# Inverter_Power_Stage.net
KiCad netlist of a schematic drawn in Altium Designer
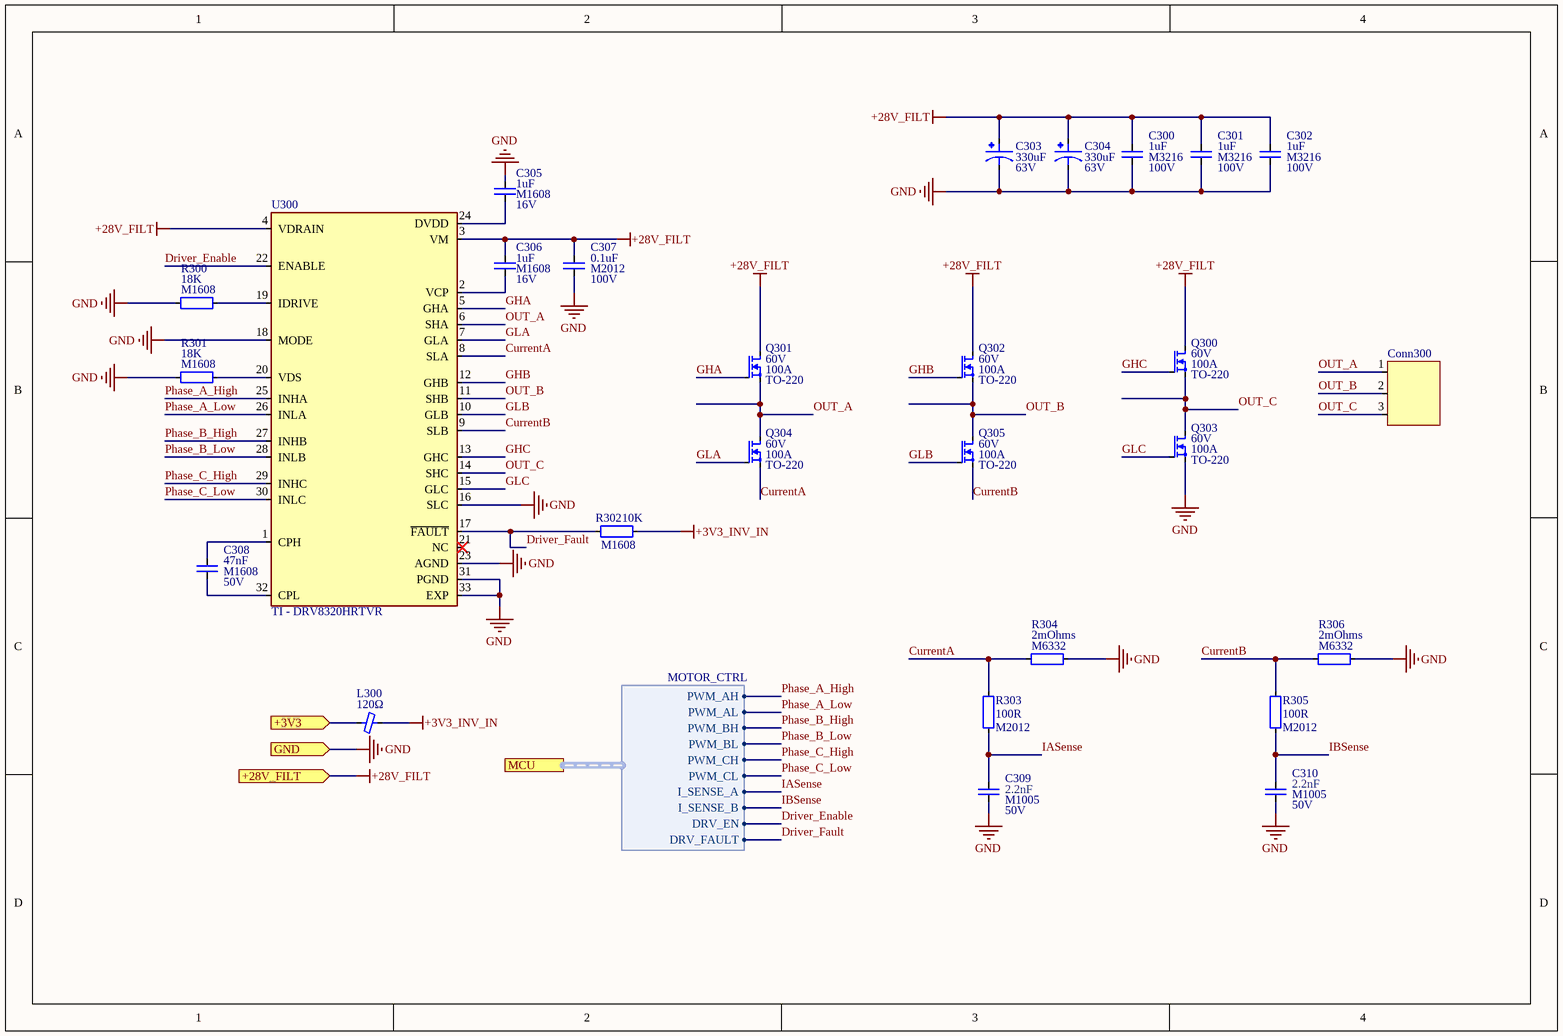
[diagram p0: Inverter_Power_Stage.SchDoc]

(export (version "E")
  (design (tool "Eeschema 10.0.6"))
  (components
    (comp (ref "C300")
      (value "1uF")
      (footprint "Capacitor_Seramic_M3216_I1206")
      (description "Cap, Cer, 1uF, 100V, M3216")
      (fields
        (field (name "TOLERANCE") "±10%")
        (field (name "MANUFACTURER PART NUMBER") "C3216X7R2A105K160AA")
        (field (name "PACKAGE") "M3216")
        (field (name "RATED VOLTAGE") "100V")
      )
      (libsource (lib "Capacitor") (part "Capacitor_Seramic"))
    )
    (comp (ref "C301")
      (value "1uF")
      (footprint "Capacitor_Seramic_M3216_I1206")
      (description "Cap, Cer, 1uF, 100V, M3216")
      (fields
        (field (name "TOLERANCE") "±10%")
        (field (name "MANUFACTURER PART NUMBER") "C3216X7R2A105K160AA")
        (field (name "PACKAGE") "M3216")
        (field (name "RATED VOLTAGE") "100V")
      )
      (libsource (lib "Capacitor") (part "Capacitor_Seramic"))
    )
    (comp (ref "C302")
      (value "1uF")
      (footprint "Capacitor_Seramic_M3216_I1206")
      (description "Cap, Cer, 1uF, 100V, M3216")
      (fields
        (field (name "TOLERANCE") "±10%")
        (field (name "MANUFACTURER PART NUMBER") "C3216X7R2A105K160AA")
        (field (name "PACKAGE") "M3216")
        (field (name "RATED VOLTAGE") "100V")
      )
      (libsource (lib "Capacitor") (part "Capacitor_Seramic"))
    )
    (comp (ref "C303")
      (value "330uF")
      (footprint "Capacitor_Aluminum_TH")
      (description "220F 63V Aluminum Electrolytic Capacitors Radial, Can 10000 Hrs @ 105C")
      (fields
        (field (name "MANUFACTURER") "Panasonic Electronic Components")
        (field (name "MANUFACTURER PART NUMBER") "EEU-FR1J331")
        (field (name "RATED VOLTAGE") "63V")
      )
      (libsource (lib "Capacitor") (part "Capacitor_Aluminum_TH"))
    )
    (comp (ref "C304")
      (value "330uF")
      (footprint "Capacitor_Aluminum_TH")
      (description "220F 63V Aluminum Electrolytic Capacitors Radial, Can 10000 Hrs @ 105C")
      (fields
        (field (name "MANUFACTURER") "Panasonic Electronic Components")
        (field (name "MANUFACTURER PART NUMBER") "EEU-FR1J331")
        (field (name "RATED VOLTAGE") "63V")
      )
      (libsource (lib "Capacitor") (part "Capacitor_Aluminum_TH"))
    )
    (comp (ref "C305")
      (value "1uF")
      (footprint "Capacitor_Seramic_M1608_I0603")
      (description "Cap, Cer, 1uF, 16V, M1608")
      (fields
        (field (name "TOLERANCE") "±10%")
        (field (name "MANUFACTURER PART NUMBER") "CL10B105KO8NNNC")
        (field (name "PACKAGE") "M1608")
        (field (name "RATED VOLTAGE") "16V")
      )
      (libsource (lib "Capacitor") (part "Capacitor_Seramic"))
    )
    (comp (ref "C306")
      (value "1uF")
      (footprint "Capacitor_Seramic_M1608_I0603")
      (description "Cap, Cer, 1uF, 16V, M1608")
      (fields
        (field (name "TOLERANCE") "±10%")
        (field (name "MANUFACTURER PART NUMBER") "CL10B105KO8NNNC")
        (field (name "PACKAGE") "M1608")
        (field (name "RATED VOLTAGE") "16V")
      )
      (libsource (lib "Capacitor") (part "Capacitor_Seramic"))
    )
    (comp (ref "C307")
      (value "0.1uF")
      (footprint "Capacitor_Seramic_M2012_I0805")
      (description "Cap, Cer, 0.1uF, 100V, M2012")
      (fields
        (field (name "TOLERANCE") "±10%")
        (field (name "MANUFACTURER PART NUMBER") "C2012X7R2A104K125AA")
        (field (name "PACKAGE") "M2012")
        (field (name "RATED VOLTAGE") "100V")
      )
      (libsource (lib "Capacitor") (part "Capacitor_Seramic"))
    )
    (comp (ref "C308")
      (value "47nF")
      (footprint "Capacitor_Seramic_M1608_I0603")
      (description "Cap, Cer, 47nF, 50V, M1608")
      (fields
        (field (name "TOLERANCE") "±10%")
        (field (name "MANUFACTURER PART NUMBER") "C3216X7R2A105K160AA")
        (field (name "PACKAGE") "M1608")
        (field (name "RATED VOLTAGE") "50V")
      )
      (libsource (lib "Capacitor") (part "Capacitor_Seramic"))
    )
    (comp (ref "C309")
      (value "2.2nF")
      (footprint "Capacitor_Seramic_M1005_I0402")
      (description "Cap, Cer, 2.2nF, 50V, M1005")
      (fields
        (field (name "TOLERANCE") "10%")
        (field (name "MANUFACTURER PART NUMBER") "GCM155R71H223KA55D")
        (field (name "PACKAGE") "M1005")
        (field (name "RATED VOLTAGE") "50V")
      )
      (libsource (lib "Capacitor") (part "Capacitor_Seramic"))
    )
    (comp (ref "C310")
      (value "2.2nF")
      (footprint "Capacitor_Seramic_M1005_I0402")
      (description "Cap, Cer, 2.2nF, 50V, M1005")
      (fields
        (field (name "TOLERANCE") "10%")
        (field (name "MANUFACTURER PART NUMBER") "GCM155R71H223KA55D")
        (field (name "PACKAGE") "M1005")
        (field (name "RATED VOLTAGE") "50V")
      )
      (libsource (lib "Capacitor") (part "Capacitor_Seramic"))
    )
    (comp (ref "Conn300")
      (value "Connector - 3P")
      (footprint "Phoenix- 3Pin, 1714968")
      (fields
        (field (name "VOLTAGE") "300V")
        (field (name "MANUFACTURER PART NUMBER") "1714968")
        (field (name "MANUFACTURER") "Phoenix Contact")
      )
      (libsource (lib "Connector - Terminal Block") (part "Connector - 3P"))
    )
    (comp (ref "L300")
      (value "120Ω")
      (footprint "Ferrite_Bead_Smd_M1608_I0603")
      (fields
        (field (name "MANUFACTURER PART NUMBER") "BLM18PG121SN1D")
        (field (name "MANUFACTURER") "Murata Electronics")
        (field (name "Comment") "Ferrite Bead")
      )
      (libsource (lib "Inductor") (part "Ferrite Bead"))
    )
    (comp (ref "Q300")
      (value "Mosfet, N-Channel - TI - CSD18532KCS")
      (footprint "TO-220-3, Mosfet, N-Channel")
      (description "Mosfet, N-Channel - Texas Instruments - CSD18532KCS")
      (fields
        (field (name "MANUFACTURER PART NUMBER") "CSD18532KCS")
        (field (name "MANUFACTURER") "Texas Instruments")
        (field (name "CURRENT") "100A")
        (field (name "VOLTAGE") "60V")
        (field (name "PACKAGE") "TO-220")
        (field (name "COMPONENTLINK1URL") "C:\\Users\\User\\OneDrive - Karadeniz Teknik University\\Masaüstü\\pcb\\kütüphane\\Datasheet\\csd18532kcs.pdf")
      )
      (libsource (lib "Transistor") (part "Mosfet, N-Channel - TI - CSD18532KCS"))
    )
    (comp (ref "Q301")
      (value "Mosfet, N-Channel - TI - CSD18532KCS")
      (footprint "TO-220-3, Mosfet, N-Channel")
      (description "Mosfet, N-Channel - Texas Instruments - CSD18532KCS")
      (fields
        (field (name "MANUFACTURER PART NUMBER") "CSD18532KCS")
        (field (name "MANUFACTURER") "Texas Instruments")
        (field (name "CURRENT") "100A")
        (field (name "VOLTAGE") "60V")
        (field (name "PACKAGE") "TO-220")
        (field (name "COMPONENTLINK1URL") "C:\\Users\\User\\OneDrive - Karadeniz Teknik University\\Masaüstü\\pcb\\kütüphane\\Datasheet\\csd18532kcs.pdf")
      )
      (libsource (lib "Transistor") (part "Mosfet, N-Channel - TI - CSD18532KCS"))
    )
    (comp (ref "Q302")
      (value "Mosfet, N-Channel - TI - CSD18532KCS")
      (footprint "TO-220-3, Mosfet, N-Channel")
      (description "Mosfet, N-Channel - Texas Instruments - CSD18532KCS")
      (fields
        (field (name "MANUFACTURER PART NUMBER") "CSD18532KCS")
        (field (name "MANUFACTURER") "Texas Instruments")
        (field (name "CURRENT") "100A")
        (field (name "VOLTAGE") "60V")
        (field (name "PACKAGE") "TO-220")
        (field (name "COMPONENTLINK1URL") "C:\\Users\\User\\OneDrive - Karadeniz Teknik University\\Masaüstü\\pcb\\kütüphane\\Datasheet\\csd18532kcs.pdf")
      )
      (libsource (lib "Transistor") (part "Mosfet, N-Channel - TI - CSD18532KCS"))
    )
    (comp (ref "Q303")
      (value "Mosfet, N-Channel - TI - CSD18532KCS")
      (footprint "TO-220-3, Mosfet, N-Channel")
      (description "Mosfet, N-Channel - Texas Instruments - CSD18532KCS")
      (fields
        (field (name "MANUFACTURER PART NUMBER") "CSD18532KCS")
        (field (name "MANUFACTURER") "Texas Instruments")
        (field (name "CURRENT") "100A")
        (field (name "VOLTAGE") "60V")
        (field (name "PACKAGE") "TO-220")
        (field (name "COMPONENTLINK1URL") "C:\\Users\\User\\OneDrive - Karadeniz Teknik University\\Masaüstü\\pcb\\kütüphane\\Datasheet\\csd18532kcs.pdf")
      )
      (libsource (lib "Transistor") (part "Mosfet, N-Channel - TI - CSD18532KCS"))
    )
    (comp (ref "Q304")
      (value "Mosfet, N-Channel - TI - CSD18532KCS")
      (footprint "TO-220-3, Mosfet, N-Channel")
      (description "Mosfet, N-Channel - Texas Instruments - CSD18532KCS")
      (fields
        (field (name "MANUFACTURER PART NUMBER") "CSD18532KCS")
        (field (name "MANUFACTURER") "Texas Instruments")
        (field (name "CURRENT") "100A")
        (field (name "VOLTAGE") "60V")
        (field (name "PACKAGE") "TO-220")
        (field (name "COMPONENTLINK1URL") "C:\\Users\\User\\OneDrive - Karadeniz Teknik University\\Masaüstü\\pcb\\kütüphane\\Datasheet\\csd18532kcs.pdf")
      )
      (libsource (lib "Transistor") (part "Mosfet, N-Channel - TI - CSD18532KCS"))
    )
    (comp (ref "Q305")
      (value "Mosfet, N-Channel - TI - CSD18532KCS")
      (footprint "TO-220-3, Mosfet, N-Channel")
      (description "Mosfet, N-Channel - Texas Instruments - CSD18532KCS")
      (fields
        (field (name "MANUFACTURER PART NUMBER") "CSD18532KCS")
        (field (name "MANUFACTURER") "Texas Instruments")
        (field (name "CURRENT") "100A")
        (field (name "VOLTAGE") "60V")
        (field (name "PACKAGE") "TO-220")
        (field (name "COMPONENTLINK1URL") "C:\\Users\\User\\OneDrive - Karadeniz Teknik University\\Masaüstü\\pcb\\kütüphane\\Datasheet\\csd18532kcs.pdf")
      )
      (libsource (lib "Transistor") (part "Mosfet, N-Channel - TI - CSD18532KCS"))
    )
    (comp (ref "R300")
      (value "18K")
      (footprint "Resistor_SMD_M1608_I0603")
      (description "Res, 18K, 1%, M1608")
      (fields
        (field (name "MANUFACTURER") "YAGEO")
        (field (name "MANUFACTURER PART NUMBER") "RC0603FR-0718KL")
        (field (name "PACKAGE") "M1608")
      )
      (libsource (lib "Resistor") (part "Resistor"))
    )
    (comp (ref "R301")
      (value "18K")
      (footprint "Resistor_SMD_M1608_I0603")
      (description "Res, 18K, 1%, M1608")
      (fields
        (field (name "MANUFACTURER") "YAGEO")
        (field (name "MANUFACTURER PART NUMBER") "RC0603FR-0718KL")
        (field (name "PACKAGE") "M1608")
      )
      (libsource (lib "Resistor") (part "Resistor"))
    )
    (comp (ref "R302")
      (value "10K")
      (footprint "Resistor_SMD_M1608_I0603")
      (description "Res, 10K, 1%, M1608")
      (fields
        (field (name "MANUFACTURER") "YAGEO")
        (field (name "MANUFACTURER PART NUMBER") "RC0603FR-0710KL")
        (field (name "PACKAGE") "M1608")
      )
      (libsource (lib "Resistor") (part "Resistor"))
    )
    (comp (ref "R303")
      (value "100R")
      (footprint "Resistor_SMD_M2012_I0805")
      (description "Res, 100R, 1%, M2012")
      (fields
        (field (name "MANUFACTURER") "Yageo")
        (field (name "MANUFACTURER PART NUMBER") "RC0805FR-07100RL")
        (field (name "PACKAGE") "M2012")
      )
      (libsource (lib "Resistor") (part "Resistor"))
    )
    (comp (ref "R304")
      (value "2mOhms")
      (footprint "Resistor_SMD_M6332_I2512")
      (description "Res, 2moHms, 1%, M6332")
      (fields
        (field (name "MANUFACTURER") "Bourns Inc.")
        (field (name "MANUFACTURER PART NUMBER") "CRF2512-FZ-R002ELF")
        (field (name "PACKAGE") "M6332")
      )
      (libsource (lib "Resistor") (part "Resistor"))
    )
    (comp (ref "R305")
      (value "100R")
      (footprint "Resistor_SMD_M2012_I0805")
      (description "Res, 100R, 1%, M2012")
      (fields
        (field (name "MANUFACTURER") "Yageo")
        (field (name "MANUFACTURER PART NUMBER") "RC0805FR-07100RL")
        (field (name "PACKAGE") "M2012")
      )
      (libsource (lib "Resistor") (part "Resistor"))
    )
    (comp (ref "R306")
      (value "2mOhms")
      (footprint "Resistor_SMD_M6332_I2512")
      (description "Res, 2moHms, 1%, M6332")
      (fields
        (field (name "MANUFACTURER") "Bourns Inc.")
        (field (name "MANUFACTURER PART NUMBER") "CRF2512-FZ-R002ELF")
        (field (name "PACKAGE") "M6332")
      )
      (libsource (lib "Resistor") (part "Resistor"))
    )
    (comp (ref "U300")
      (value "TI - DRV8320HRTVR")
      (footprint "QFN-48 5mm x 5mm")
      (description "65-V max 3-phase smart gate driver")
      (fields
        (field (name "MF") "Texas Instruments")
        (field (name "MP") "DRV8320HRTVR")
        (field (name "COMPONENTLINK1URL") "C:\\Users\\User\\OneDrive - Karadeniz Teknik University\\Masaüstü\\pcb\\kütüphane\\Datasheet\\drv8320.pdf")
      )
      (libsource (lib "IC - Driver - Motor") (part "TI - DRV8320HRTVR"))
    )
  )
  (nets
    (net (code "2") (name "+3V3_INV_IN") (class "Default")
      (node (ref "L300") (pin "2") (pinfunction "2_2") (pintype "passive"))
      (node (ref "R302") (pin "2") (pinfunction "2_2") (pintype "passive"))
    )
    (net (code "3") (name "+28V_FILT") (class "Default")
      (node (ref "C300") (pin "1") (pinfunction "1_1") (pintype "passive"))
      (node (ref "C301") (pin "1") (pinfunction "1_1") (pintype "passive"))
      (node (ref "C302") (pin "1") (pinfunction "1_1") (pintype "passive"))
      (node (ref "C303") (pin "P") (pinfunction "P_P") (pintype "passive"))
      (node (ref "C304") (pin "P") (pinfunction "P_P") (pintype "passive"))
      (node (ref "C306") (pin "1") (pinfunction "1_1") (pintype "passive"))
      (node (ref "C307") (pin "1") (pinfunction "1_1") (pintype "passive"))
      (node (ref "Q300") (pin "D") (pinfunction "D_D") (pintype "passive"))
      (node (ref "Q301") (pin "D") (pinfunction "D_D") (pintype "passive"))
      (node (ref "Q302") (pin "D") (pinfunction "D_D") (pintype "passive"))
      (node (ref "U300") (pin "3") (pinfunction "VM_3") (pintype "passive"))
      (node (ref "U300") (pin "4") (pinfunction "VDRAIN_4") (pintype "passive"))
    )
    (net (code "4") (name "/+3V3") (class "Default")
      (node (ref "L300") (pin "1") (pinfunction "1_1") (pintype "passive"))
    )
    (net (code "5") (name "/CurrentA") (class "Default")
      (node (ref "Q304") (pin "S") (pinfunction "S_S") (pintype "passive"))
      (node (ref "R303") (pin "2") (pinfunction "2_2") (pintype "passive"))
      (node (ref "R304") (pin "1") (pinfunction "1_1") (pintype "passive"))
      (node (ref "U300") (pin "8") (pinfunction "SLA_8") (pintype "passive"))
    )
    (net (code "6") (name "/CurrentB") (class "Default")
      (node (ref "Q305") (pin "S") (pinfunction "S_S") (pintype "passive"))
      (node (ref "R305") (pin "2") (pinfunction "2_2") (pintype "passive"))
      (node (ref "R306") (pin "1") (pinfunction "1_1") (pintype "passive"))
      (node (ref "U300") (pin "9") (pinfunction "SLB_9") (pintype "passive"))
    )
    (net (code "7") (name "/Driver_Enable") (class "Default")
      (node (ref "U300") (pin "22") (pinfunction "ENABLE_22") (pintype "passive"))
    )
    (net (code "8") (name "/Driver_Fault") (class "Default")
      (node (ref "R302") (pin "1") (pinfunction "1_1") (pintype "passive"))
      (node (ref "U300") (pin "17") (pinfunction "~{FAULT}_17") (pintype "passive"))
    )
    (net (code "9") (name "/GHA") (class "Default")
      (node (ref "Q301") (pin "G") (pinfunction "G_G") (pintype "passive"))
      (node (ref "U300") (pin "5") (pinfunction "GHA_5") (pintype "passive"))
    )
    (net (code "10") (name "/GHB") (class "Default")
      (node (ref "Q302") (pin "G") (pinfunction "G_G") (pintype "passive"))
      (node (ref "U300") (pin "12") (pinfunction "GHB_12") (pintype "passive"))
    )
    (net (code "11") (name "/GHC") (class "Default")
      (node (ref "Q300") (pin "G") (pinfunction "G_G") (pintype "passive"))
      (node (ref "U300") (pin "13") (pinfunction "GHC_13") (pintype "passive"))
    )
    (net (code "12") (name "/GLA") (class "Default")
      (node (ref "Q304") (pin "G") (pinfunction "G_G") (pintype "passive"))
      (node (ref "U300") (pin "7") (pinfunction "GLA_7") (pintype "passive"))
    )
    (net (code "13") (name "/GLB") (class "Default")
      (node (ref "Q305") (pin "G") (pinfunction "G_G") (pintype "passive"))
      (node (ref "U300") (pin "10") (pinfunction "GLB_10") (pintype "passive"))
    )
    (net (code "14") (name "/GLC") (class "Default")
      (node (ref "Q303") (pin "G") (pinfunction "G_G") (pintype "passive"))
      (node (ref "U300") (pin "15") (pinfunction "GLC_15") (pintype "passive"))
    )
    (net (code "15") (name "/IASense") (class "Default")
      (node (ref "C309") (pin "2") (pinfunction "2_2") (pintype "passive"))
      (node (ref "R303") (pin "1") (pinfunction "1_1") (pintype "passive"))
    )
    (net (code "16") (name "/IBSense") (class "Default")
      (node (ref "C310") (pin "1") (pinfunction "1_1") (pintype "passive"))
      (node (ref "R305") (pin "1") (pinfunction "1_1") (pintype "passive"))
    )
    (net (code "17") (name "/OUT_A") (class "Default")
      (node (ref "Conn300") (pin "1") (pinfunction "1_1") (pintype "passive"))
      (node (ref "Q301") (pin "S") (pinfunction "S_S") (pintype "passive"))
      (node (ref "Q304") (pin "D") (pinfunction "D_D") (pintype "passive"))
      (node (ref "U300") (pin "6") (pinfunction "SHA_6") (pintype "passive"))
    )
    (net (code "18") (name "/OUT_B") (class "Default")
      (node (ref "Conn300") (pin "2") (pinfunction "2_2") (pintype "passive"))
      (node (ref "Q302") (pin "S") (pinfunction "S_S") (pintype "passive"))
      (node (ref "Q305") (pin "D") (pinfunction "D_D") (pintype "passive"))
      (node (ref "U300") (pin "11") (pinfunction "SHB_11") (pintype "passive"))
    )
    (net (code "19") (name "/OUT_C") (class "Default")
      (node (ref "Conn300") (pin "3") (pinfunction "3_3") (pintype "passive"))
      (node (ref "Q300") (pin "S") (pinfunction "S_S") (pintype "passive"))
      (node (ref "Q303") (pin "D") (pinfunction "D_D") (pintype "passive"))
      (node (ref "U300") (pin "14") (pinfunction "SHC_14") (pintype "passive"))
    )
    (net (code "20") (name "/Phase_A_High") (class "Default")
      (node (ref "U300") (pin "25") (pinfunction "INHA_25") (pintype "passive"))
    )
    (net (code "21") (name "/Phase_A_Low") (class "Default")
      (node (ref "U300") (pin "26") (pinfunction "INLA_26") (pintype "passive"))
    )
    (net (code "22") (name "/Phase_B_High") (class "Default")
      (node (ref "U300") (pin "27") (pinfunction "INHB_27") (pintype "passive"))
    )
    (net (code "23") (name "/Phase_B_Low") (class "Default")
      (node (ref "U300") (pin "28") (pinfunction "INLB_28") (pintype "passive"))
    )
    (net (code "24") (name "/Phase_C_High") (class "Default")
      (node (ref "U300") (pin "29") (pinfunction "INHC_29") (pintype "passive"))
    )
    (net (code "25") (name "/Phase_C_Low") (class "Default")
      (node (ref "U300") (pin "30") (pinfunction "INLC_30") (pintype "passive"))
    )
    (net (code "27") (name "GND") (class "Default")
      (node (ref "C300") (pin "2") (pinfunction "2_2") (pintype "passive"))
      (node (ref "C301") (pin "2") (pinfunction "2_2") (pintype "passive"))
      (node (ref "C302") (pin "2") (pinfunction "2_2") (pintype "passive"))
      (node (ref "C303") (pin "N") (pinfunction "N_N") (pintype "passive"))
      (node (ref "C304") (pin "N") (pinfunction "N_N") (pintype "passive"))
      (node (ref "C305") (pin "1") (pinfunction "1_1") (pintype "passive"))
      (node (ref "C307") (pin "2") (pinfunction "2_2") (pintype "passive"))
      (node (ref "C309") (pin "1") (pinfunction "1_1") (pintype "passive"))
      (node (ref "C310") (pin "2") (pinfunction "2_2") (pintype "passive"))
      (node (ref "Q303") (pin "S") (pinfunction "S_S") (pintype "passive"))
      (node (ref "R300") (pin "1") (pinfunction "1_1") (pintype "passive"))
      (node (ref "R301") (pin "1") (pinfunction "1_1") (pintype "passive"))
      (node (ref "R304") (pin "2") (pinfunction "2_2") (pintype "passive"))
      (node (ref "R306") (pin "2") (pinfunction "2_2") (pintype "passive"))
      (node (ref "U300") (pin "16") (pinfunction "SLC_16") (pintype "passive"))
      (node (ref "U300") (pin "18") (pinfunction "MODE_18") (pintype "passive"))
      (node (ref "U300") (pin "23") (pinfunction "AGND_23") (pintype "passive"))
      (node (ref "U300") (pin "31") (pinfunction "PGND_31") (pintype "passive"))
      (node (ref "U300") (pin "33") (pinfunction "EXP_33") (pintype "passive"))
    )
    (net (code "28") (name "Net-(U300-CPH)") (class "Default")
      (node (ref "C308") (pin "1") (pinfunction "1_1") (pintype "passive"))
      (node (ref "U300") (pin "1") (pinfunction "CPH_1") (pintype "passive"))
    )
    (net (code "29") (name "Net-(U300-CPL)") (class "Default")
      (node (ref "C308") (pin "2") (pinfunction "2_2") (pintype "passive"))
      (node (ref "U300") (pin "32") (pinfunction "CPL_32") (pintype "passive"))
    )
    (net (code "30") (name "Net-(U300-DVDD)") (class "Default")
      (node (ref "C305") (pin "2") (pinfunction "2_2") (pintype "passive"))
      (node (ref "U300") (pin "24") (pinfunction "DVDD_24") (pintype "passive"))
    )
    (net (code "31") (name "Net-(U300-IDRIVE)") (class "Default")
      (node (ref "R300") (pin "2") (pinfunction "2_2") (pintype "passive"))
      (node (ref "U300") (pin "19") (pinfunction "IDRIVE_19") (pintype "passive"))
    )
    (net (code "32") (name "Net-(U300-VCP)") (class "Default")
      (node (ref "C306") (pin "2") (pinfunction "2_2") (pintype "passive"))
      (node (ref "U300") (pin "2") (pinfunction "VCP_2") (pintype "passive"))
    )
    (net (code "33") (name "Net-(U300-VDS)") (class "Default")
      (node (ref "R301") (pin "2") (pinfunction "2_2") (pintype "passive"))
      (node (ref "U300") (pin "20") (pinfunction "VDS_20") (pintype "passive"))
    )
    (net (code "34") (name "unconnected-(U300-NC-Pad21)") (class "Default")
      (node (ref "U300") (pin "21") (pinfunction "NC_21") (pintype "passive+no_connect"))
    )
  )
)
